# gpsfreq.net
KiCad netlist of a schematic drawn in EAGLE
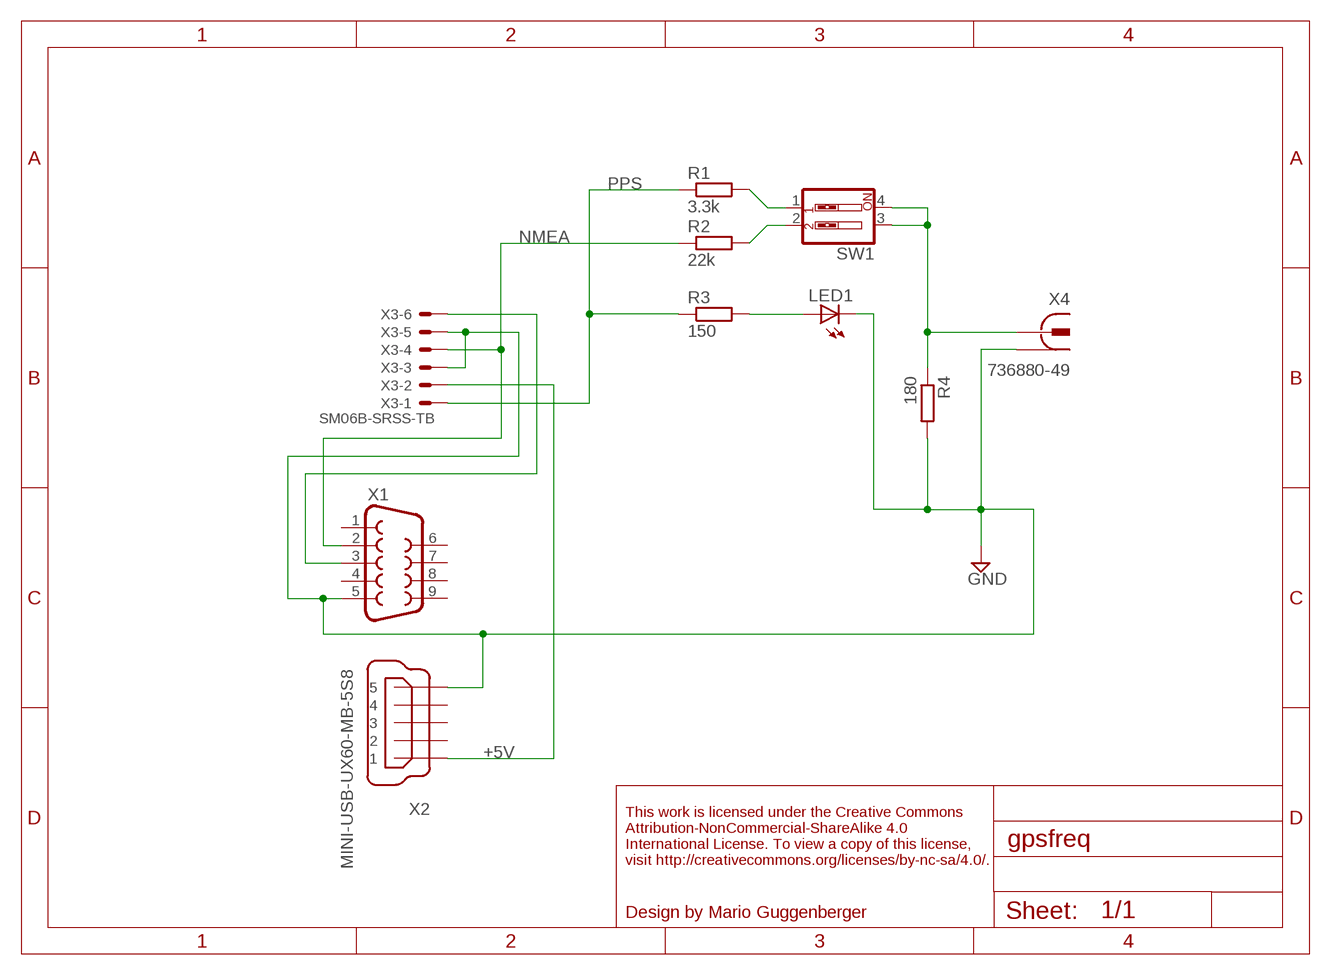
[diagram p0: schematic, sheet 1]

(export (version "E")
  (design (tool "Eeschema 10.0.6"))
  (components
    (comp (ref "LED1")
      (value "LED3MM")
      (footprint "eagle-import:LED3MM")
      (libsource (lib "eagle-import") (part "LED3MM"))
    )
    (comp (ref "R1")
      (value "3.3k")
      (footprint "eagle-import:0204_7")
      (libsource (lib "eagle-import") (part "R-EU_0204_7"))
    )
    (comp (ref "R2")
      (value "22k")
      (footprint "eagle-import:0204_7")
      (libsource (lib "eagle-import") (part "R-EU_0204_7"))
    )
    (comp (ref "R3")
      (value "150")
      (footprint "eagle-import:0204_7")
      (libsource (lib "eagle-import") (part "R-EU_0204_7"))
    )
    (comp (ref "R4")
      (value "180")
      (footprint "eagle-import:0204_7")
      (libsource (lib "eagle-import") (part "R-EU_0204_7"))
    )
    (comp (ref "SW1")
      (value "SW_DIP-2")
      (footprint "eagle-import:EDG-02")
      (libsource (lib "eagle-import") (part "SW_DIP-2"))
    )
    (comp (ref "X1")
      (value "F09H")
      (footprint "eagle-import:F09H")
      (libsource (lib "eagle-import") (part "F09H"))
    )
    (comp (ref "X2")
      (value "MINI-USB-UX60-MB-5S8")
      (footprint "eagle-import:UX60-MB-5S8")
      (libsource (lib "eagle-import") (part "MINI-USB-UX60-MB-5S8"))
    )
    (comp (ref "X3")
      (value "SM06B-SRSS-TB")
      (footprint "eagle-import:SM06B-SRSS-TB")
      (libsource (lib "eagle-import") (part "?M06B-SRSS-TBS"))
    )
    (comp (ref "X4")
      (value "736880-49")
      (footprint "eagle-import:736880-49")
      (libsource (lib "eagle-import") (part "736880-49"))
    )
  )
  (nets
    (net (code "1") (name "/+5V") (class "Default")
      (node (ref "X2") (pin "1") (pinfunction "1_1") (pintype "input"))
      (node (ref "X3") (pin "2") (pinfunction "S_2") (pintype "passive"))
    )
    (net (code "2") (name "/NMEA") (class "Default")
      (node (ref "R2") (pin "1") (pinfunction "1_1") (pintype "passive"))
      (node (ref "X1") (pin "2") (pinfunction "2_2") (pintype "passive"))
      (node (ref "X3") (pin "4") (pinfunction "S_4") (pintype "passive"))
    )
    (net (code "3") (name "/PPS") (class "Default")
      (node (ref "R1") (pin "1") (pinfunction "1_1") (pintype "passive"))
      (node (ref "R3") (pin "1") (pinfunction "1_1") (pintype "passive"))
      (node (ref "X3") (pin "1") (pinfunction "S_1") (pintype "passive"))
    )
    (net (code "4") (name "GND") (class "Default")
      (node (ref "LED1") (pin "K") (pinfunction "C_K") (pintype "passive"))
      (node (ref "R4") (pin "2") (pinfunction "2_2") (pintype "passive"))
      (node (ref "X1") (pin "5") (pinfunction "5_5") (pintype "passive"))
      (node (ref "X2") (pin "5") (pinfunction "5_5") (pintype "input"))
      (node (ref "X3") (pin "3") (pinfunction "S_3") (pintype "passive"))
      (node (ref "X3") (pin "5") (pinfunction "S_5") (pintype "passive"))
      (node (ref "X4") (pin "1") (pinfunction "1_1") (pintype "passive"))
      (node (ref "X4") (pin "1@1") (pinfunction "1_1@1") (pintype "passive"))
      (node (ref "X4") (pin "1@2") (pinfunction "1_1@2") (pintype "passive"))
    )
    (net (code "5") (name "Net-(LED1-PadA)") (class "Default")
      (node (ref "LED1") (pin "A") (pinfunction "A_A") (pintype "passive"))
      (node (ref "R3") (pin "2") (pinfunction "2_2") (pintype "passive"))
    )
    (net (code "6") (name "Net-(R1-Pad2)") (class "Default")
      (node (ref "R1") (pin "2") (pinfunction "2_2") (pintype "passive"))
      (node (ref "SW1") (pin "1") (pinfunction "1_1") (pintype "passive"))
    )
    (net (code "7") (name "Net-(R2-Pad2)") (class "Default")
      (node (ref "R2") (pin "2") (pinfunction "2_2") (pintype "passive"))
      (node (ref "SW1") (pin "2") (pinfunction "2_2") (pintype "passive"))
    )
    (net (code "8") (name "Net-(R4-Pad1)") (class "Default")
      (node (ref "R4") (pin "1") (pinfunction "1_1") (pintype "passive"))
      (node (ref "SW1") (pin "3") (pinfunction "3_3") (pintype "passive"))
      (node (ref "SW1") (pin "4") (pinfunction "4_4") (pintype "passive"))
      (node (ref "X4") (pin "2") (pinfunction "2_2") (pintype "passive"))
    )
    (net (code "9") (name "Net-(X3F-S)") (class "Default")
      (node (ref "X1") (pin "3") (pinfunction "3_3") (pintype "passive"))
      (node (ref "X3") (pin "6") (pinfunction "S_6") (pintype "passive"))
    )
    (net (code "10") (name "unconnected-(X1-Pad1)") (class "Default")
      (node (ref "X1") (pin "1") (pinfunction "1_1") (pintype "passive"))
    )
    (net (code "11") (name "unconnected-(X1-Pad4)") (class "Default")
      (node (ref "X1") (pin "4") (pinfunction "4_4") (pintype "passive"))
    )
    (net (code "12") (name "unconnected-(X1-Pad6)") (class "Default")
      (node (ref "X1") (pin "6") (pinfunction "6_6") (pintype "passive"))
    )
    (net (code "13") (name "unconnected-(X1-Pad7)") (class "Default")
      (node (ref "X1") (pin "7") (pinfunction "7_7") (pintype "passive"))
    )
    (net (code "14") (name "unconnected-(X1-Pad8)") (class "Default")
      (node (ref "X1") (pin "8") (pinfunction "8_8") (pintype "passive"))
    )
    (net (code "15") (name "unconnected-(X1-Pad9)") (class "Default")
      (node (ref "X1") (pin "9") (pinfunction "9_9") (pintype "passive"))
    )
    (net (code "16") (name "unconnected-(X2-Pad2)") (class "Default")
      (node (ref "X2") (pin "2") (pinfunction "2_2") (pintype "input"))
    )
    (net (code "17") (name "unconnected-(X2-Pad3)") (class "Default")
      (node (ref "X2") (pin "3") (pinfunction "3_3") (pintype "input"))
    )
    (net (code "18") (name "unconnected-(X2-Pad4)") (class "Default")
      (node (ref "X2") (pin "4") (pinfunction "4_4") (pintype "input"))
    )
  )
)
